# 3_baseband.net
KiCad netlist of a schematic drawn in Altium Designer
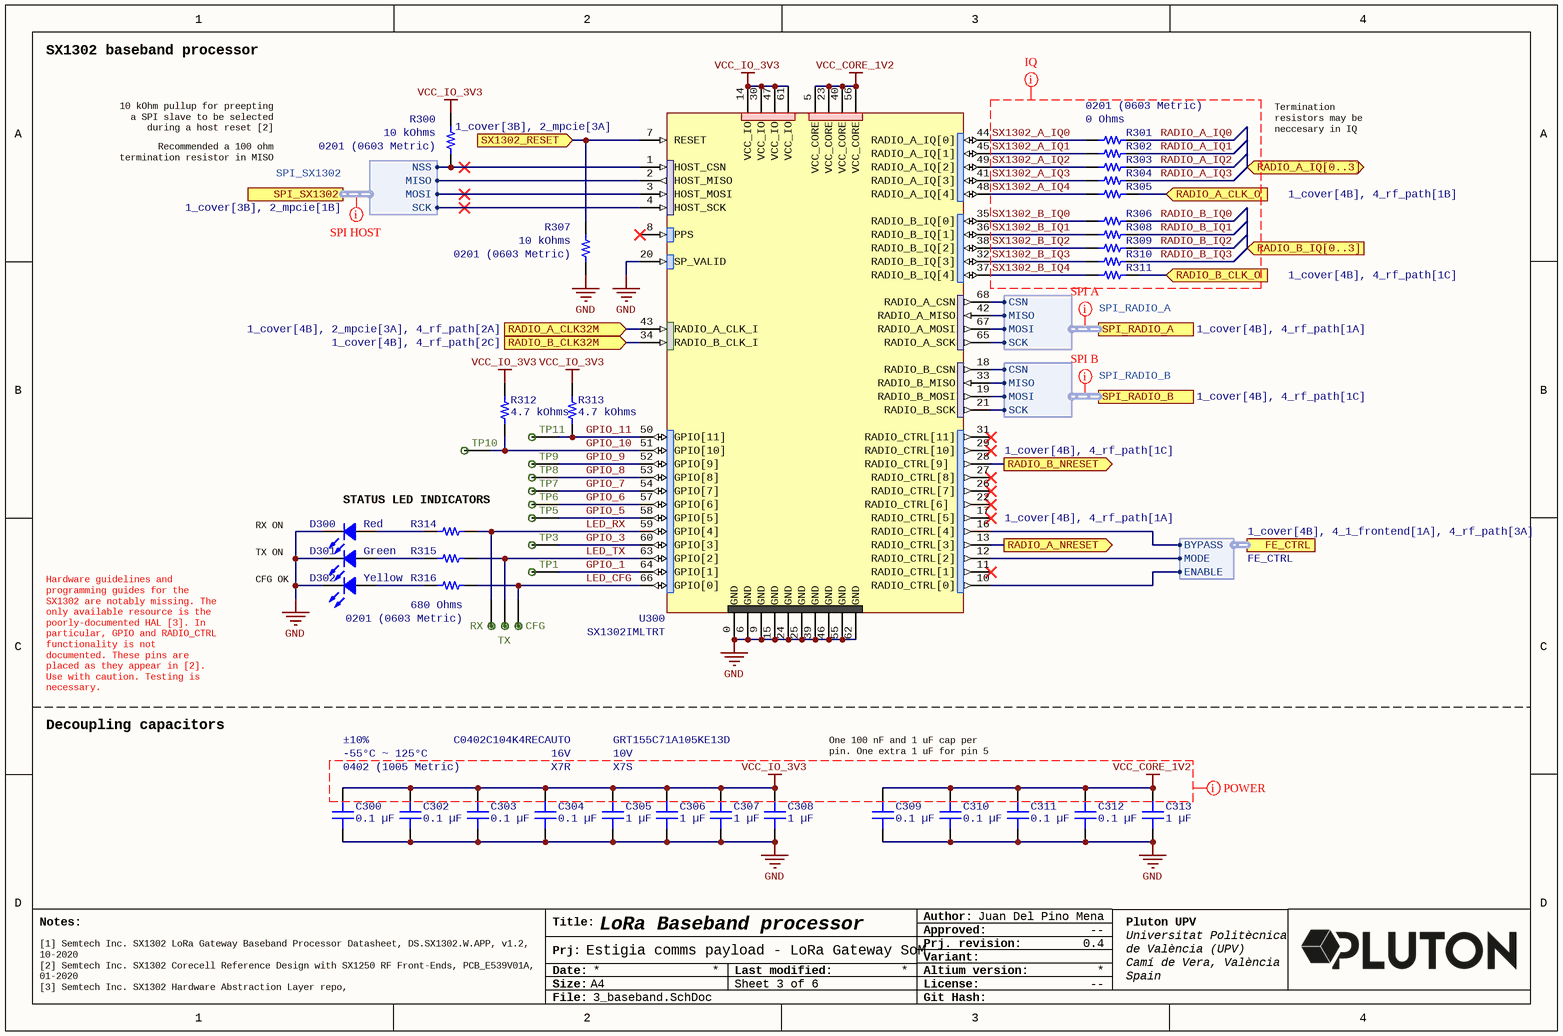
[diagram p0: 3_baseband.SchDoc]

(export (version "E")
  (design (tool "Eeschema 10.0.6"))
  (components
    (comp (ref "C300")
      (value "0.1 µF")
      (footprint "CAP 0402_1005")
      (description "CAP CER 0402 0.1UF 16V X7R 10%")
      (fields
        (field (name "PART NUMBER") "C0402C104K4RECAUTO")
        (field (name "MANUFACTURER") "KEMET")
        (field (name "OPERATING TEMPERATURE") "-55°C ~ 125°C")
        (field (name "PACKAGE / CASE") "0402 (1005 Metric)")
        (field (name "TEMPERATURE COEFFICIENT") "X7R")
        (field (name "TOLERANCE") "±10%")
        (field (name "VOLTAGE - RATED") "16V")
      )
      (libsource (lib "Celestial Altium Library - altium_library") (part "Capacitor"))
    )
    (comp (ref "C302")
      (value "0.1 µF")
      (footprint "CAP 0402_1005")
      (description "CAP CER 0402 0.1UF 16V X7R 10%")
      (fields (field (name "PART NUMBER") "C0402C104K4RECAUTO") (field (name "MANUFACTURER") "KEMET"))
      (libsource (lib "Celestial Altium Library - altium_library") (part "Capacitor"))
    )
    (comp (ref "C303")
      (value "0.1 µF")
      (footprint "CAP 0402_1005")
      (description "CAP CER 0402 0.1UF 16V X7R 10%")
      (fields (field (name "PART NUMBER") "C0402C104K4RECAUTO") (field (name "MANUFACTURER") "KEMET"))
      (libsource (lib "Celestial Altium Library - altium_library") (part "Capacitor"))
    )
    (comp (ref "C304")
      (value "0.1 µF")
      (footprint "CAP 0402_1005")
      (description "CAP CER 0402 0.1UF 16V X7R 10%")
      (fields (field (name "PART NUMBER") "C0402C104K4RECAUTO") (field (name "MANUFACTURER") "KEMET"))
      (libsource (lib "Celestial Altium Library - altium_library") (part "Capacitor"))
    )
    (comp (ref "C305")
      (value "1 µF")
      (footprint "CAP 0402_1005")
      (description "CAP CER 1UF 10V X7S 0402")
      (fields
        (field (name "PART NUMBER") "GRT155C71A105KE13D")
        (field (name "MANUFACTURER") "Murata Electronics")
        (field (name "TEMPERATURE COEFFICIENT") "X7S")
        (field (name "TOLERANCE") "±10%")
        (field (name "VOLTAGE - RATED") "10V")
      )
      (libsource (lib "Celestial Altium Library - altium_library") (part "Capacitor"))
    )
    (comp (ref "C306")
      (value "1 µF")
      (footprint "CAP 0402_1005")
      (description "CAP CER 1UF 10V X7S 0402")
      (fields
        (field (name "PART NUMBER") "GRT155C71A105KE13D")
        (field (name "MANUFACTURER") "Murata Electronics")
      )
      (libsource (lib "Celestial Altium Library - altium_library") (part "Capacitor"))
    )
    (comp (ref "C307")
      (value "1 µF")
      (footprint "CAP 0402_1005")
      (description "CAP CER 1UF 10V X7S 0402")
      (fields
        (field (name "PART NUMBER") "GRT155C71A105KE13D")
        (field (name "MANUFACTURER") "Murata Electronics")
      )
      (libsource (lib "Celestial Altium Library - altium_library") (part "Capacitor"))
    )
    (comp (ref "C308")
      (value "1 µF")
      (footprint "CAP 0402_1005")
      (description "CAP CER 1UF 10V X7S 0402")
      (fields
        (field (name "PART NUMBER") "GRT155C71A105KE13D")
        (field (name "MANUFACTURER") "Murata Electronics")
      )
      (libsource (lib "Celestial Altium Library - altium_library") (part "Capacitor"))
    )
    (comp (ref "C309")
      (value "0.1 µF")
      (footprint "CAP 0402_1005")
      (description "CAP CER 0402 0.1UF 16V X7R 10%")
      (fields (field (name "PART NUMBER") "C0402C104K4RECAUTO") (field (name "MANUFACTURER") "KEMET"))
      (libsource (lib "Celestial Altium Library - altium_library") (part "Capacitor"))
    )
    (comp (ref "C310")
      (value "0.1 µF")
      (footprint "CAP 0402_1005")
      (description "CAP CER 0402 0.1UF 16V X7R 10%")
      (fields (field (name "PART NUMBER") "C0402C104K4RECAUTO") (field (name "MANUFACTURER") "KEMET"))
      (libsource (lib "Celestial Altium Library - altium_library") (part "Capacitor"))
    )
    (comp (ref "C311")
      (value "0.1 µF")
      (footprint "CAP 0402_1005")
      (description "CAP CER 0402 0.1UF 16V X7R 10%")
      (fields (field (name "PART NUMBER") "C0402C104K4RECAUTO") (field (name "MANUFACTURER") "KEMET"))
      (libsource (lib "Celestial Altium Library - altium_library") (part "Capacitor"))
    )
    (comp (ref "C312")
      (value "0.1 µF")
      (footprint "CAP 0402_1005")
      (description "CAP CER 0402 0.1UF 16V X7R 10%")
      (fields (field (name "PART NUMBER") "C0402C104K4RECAUTO") (field (name "MANUFACTURER") "KEMET"))
      (libsource (lib "Celestial Altium Library - altium_library") (part "Capacitor"))
    )
    (comp (ref "C313")
      (value "1 µF")
      (footprint "CAP 0402_1005")
      (description "CAP CER 1UF 10V X7S 0402")
      (fields
        (field (name "PART NUMBER") "GRT155C71A105KE13D")
        (field (name "MANUFACTURER") "Murata Electronics")
      )
      (libsource (lib "Celestial Altium Library - altium_library") (part "Capacitor"))
    )
    (comp (ref "CFG")
      (value "~")
      (footprint "testpoints:testpoint_via")
      (description "Test point, thru-hole")
      (libsource (lib "testpoints") (part "TestPoint-VIA"))
    )
    (comp (ref "D300")
      (value "Red")
      (footprint "LED 0402_1005 RED")
      (description "LED RED CLEAR 2SMD")
      (fields
        (field (name "PART NUMBER") "EAST10053RA0")
        (field (name "COLOR") "Red")
        (field (name "MANUFACTURER") "Everlight Electronics Co Ltd")
      )
      (libsource (lib "Celestial Altium Library - altium_library") (part "LED"))
    )
    (comp (ref "D301")
      (value "Green")
      (footprint "LED 0402_1005 GREEN")
      (description "LED GREEN CLEAR 2SMD")
      (fields
        (field (name "PART NUMBER") "EAST10052GA0")
        (field (name "COLOR") "Green")
        (field (name "MANUFACTURER") "Everlight Electronics Co Ltd")
      )
      (libsource (lib "Celestial Altium Library - altium_library") (part "LED"))
    )
    (comp (ref "D302")
      (value "Yellow")
      (footprint "LED 0402_1005 YELLOW")
      (description "LED YELLOW CLEAR 1005 SMD")
      (fields
        (field (name "PART NUMBER") "FHY1105P-TR")
        (field (name "COLOR") "Yellow")
        (field (name "MANUFACTURER") "Stanley Electric Co")
      )
      (libsource (lib "Celestial Altium Library - altium_library") (part "LED"))
    )
    (comp (ref "R300")
      (value "10 kOhms")
      (footprint "RES 0201_0603")
      (description "RES SMD 10K OHM 1% 1/20W 0201")
      (fields
        (field (name "PART NUMBER") "AF0201FR-0710KL")
        (field (name "MANUFACTURER") "Yageo")
        (field (name "PACKAGE / CASE") "0201 (0603 Metric)")
      )
      (libsource (lib "Celestial Altium Library - altium_library") (part "Resistor"))
    )
    (comp (ref "R301")
      (value "0 Ohms")
      (footprint "RES 0201_0603")
      (description "RES SMD 0 OHM JUMPER 1/20W 0201")
      (fields
        (field (name "PART NUMBER") "AC0201JR-070RL")
        (field (name "DEVICE PACKAGE") "0201 (0603 Metric)")
        (field (name "MANUFACTURER") "Yageo")
      )
      (libsource (lib "Celestial Altium Library - altium_library") (part "Resistor"))
    )
    (comp (ref "R302")
      (value "0 Ohms")
      (footprint "RES 0201_0603")
      (description "RES SMD 0 OHM JUMPER 1/20W 0201")
      (fields (field (name "PART NUMBER") "AC0201JR-070RL") (field (name "MANUFACTURER") "Yageo"))
      (libsource (lib "Celestial Altium Library - altium_library") (part "Resistor"))
    )
    (comp (ref "R303")
      (value "0 Ohms")
      (footprint "RES 0201_0603")
      (description "RES SMD 0 OHM JUMPER 1/20W 0201")
      (fields (field (name "PART NUMBER") "AC0201JR-070RL") (field (name "MANUFACTURER") "Yageo"))
      (libsource (lib "Celestial Altium Library - altium_library") (part "Resistor"))
    )
    (comp (ref "R304")
      (value "0 Ohms")
      (footprint "RES 0201_0603")
      (description "RES SMD 0 OHM JUMPER 1/20W 0201")
      (fields (field (name "PART NUMBER") "AC0201JR-070RL") (field (name "MANUFACTURER") "Yageo"))
      (libsource (lib "Celestial Altium Library - altium_library") (part "Resistor"))
    )
    (comp (ref "R305")
      (value "0 Ohms")
      (footprint "RES 0201_0603")
      (description "RES SMD 0 OHM JUMPER 1/20W 0201")
      (fields (field (name "PART NUMBER") "AC0201JR-070RL") (field (name "MANUFACTURER") "Yageo"))
      (libsource (lib "Celestial Altium Library - altium_library") (part "Resistor"))
    )
    (comp (ref "R306")
      (value "0 Ohms")
      (footprint "RES 0201_0603")
      (description "RES SMD 0 OHM JUMPER 1/20W 0201")
      (fields (field (name "PART NUMBER") "AC0201JR-070RL") (field (name "MANUFACTURER") "Yageo"))
      (libsource (lib "Celestial Altium Library - altium_library") (part "Resistor"))
    )
    (comp (ref "R307")
      (value "10 kOhms")
      (footprint "RES 0201_0603")
      (description "RES SMD 10K OHM 1% 1/20W 0201")
      (fields
        (field (name "PART NUMBER") "AF0201FR-0710KL")
        (field (name "MANUFACTURER") "Yageo")
        (field (name "PACKAGE / CASE") "0201 (0603 Metric)")
      )
      (libsource (lib "Celestial Altium Library - altium_library") (part "Resistor"))
    )
    (comp (ref "R308")
      (value "0 Ohms")
      (footprint "RES 0201_0603")
      (description "RES SMD 0 OHM JUMPER 1/20W 0201")
      (fields (field (name "PART NUMBER") "AC0201JR-070RL") (field (name "MANUFACTURER") "Yageo"))
      (libsource (lib "Celestial Altium Library - altium_library") (part "Resistor"))
    )
    (comp (ref "R309")
      (value "0 Ohms")
      (footprint "RES 0201_0603")
      (description "RES SMD 0 OHM JUMPER 1/20W 0201")
      (fields (field (name "PART NUMBER") "AC0201JR-070RL") (field (name "MANUFACTURER") "Yageo"))
      (libsource (lib "Celestial Altium Library - altium_library") (part "Resistor"))
    )
    (comp (ref "R310")
      (value "0 Ohms")
      (footprint "RES 0201_0603")
      (description "RES SMD 0 OHM JUMPER 1/20W 0201")
      (fields (field (name "PART NUMBER") "AC0201JR-070RL") (field (name "MANUFACTURER") "Yageo"))
      (libsource (lib "Celestial Altium Library - altium_library") (part "Resistor"))
    )
    (comp (ref "R311")
      (value "0 Ohms")
      (footprint "RES 0201_0603")
      (description "RES SMD 0 OHM JUMPER 1/20W 0201")
      (fields (field (name "PART NUMBER") "AC0201JR-070RL") (field (name "MANUFACTURER") "Yageo"))
      (libsource (lib "Celestial Altium Library - altium_library") (part "Resistor"))
    )
    (comp (ref "R312")
      (value "4.7 kOhms")
      (footprint "RES 0201_0603")
      (description "RES SMD 4.7K OHM 1% 1/20W 0201")
      (fields (field (name "PART NUMBER") "AC0201FR-074K7L") (field (name "MANUFACTURER") "Yageo"))
      (libsource (lib "Celestial Altium Library - altium_library") (part "Resistor"))
    )
    (comp (ref "R313")
      (value "4.7 kOhms")
      (footprint "RES 0201_0603")
      (description "RES SMD 4.7K OHM 1% 1/20W 0201")
      (fields (field (name "PART NUMBER") "AC0201FR-074K7L") (field (name "MANUFACTURER") "Yageo"))
      (libsource (lib "Celestial Altium Library - altium_library") (part "Resistor"))
    )
    (comp (ref "R314")
      (value "680 Ohms")
      (footprint "RES 0201_0603")
      (description "RES 680 OHM 5% 1/20W 0201")
      (fields (field (name "PART NUMBER") "RC0201JR-07680RL") (field (name "MANUFACTURER") "Yageo"))
      (libsource (lib "Celestial Altium Library - altium_library") (part "Resistor"))
    )
    (comp (ref "R315")
      (value "680 Ohms")
      (footprint "RES 0201_0603")
      (description "RES 680 OHM 5% 1/20W 0201")
      (fields (field (name "PART NUMBER") "RC0201JR-07680RL") (field (name "MANUFACTURER") "Yageo"))
      (libsource (lib "Celestial Altium Library - altium_library") (part "Resistor"))
    )
    (comp (ref "R316")
      (value "680 Ohms")
      (footprint "RES 0201_0603")
      (description "RES 680 OHM 5% 1/20W 0201")
      (fields
        (field (name "PART NUMBER") "RC0201JR-07680RL")
        (field (name "DEVICE PACKAGE") "0201 (0603 Metric)")
        (field (name "MANUFACTURER") "Yageo")
      )
      (libsource (lib "Celestial Altium Library - altium_library") (part "Resistor"))
    )
    (comp (ref "RX")
      (value "~")
      (footprint "testpoints:testpoint_via")
      (description "Test point, thru-hole")
      (libsource (lib "testpoints") (part "TestPoint-VIA"))
    )
    (comp (ref "TP1")
      (value "~")
      (footprint "testpoints:testpoint_pad")
      (description "Test point, pad")
      (libsource (lib "testpoints") (part "TestPoint-PAD"))
    )
    (comp (ref "TP3")
      (value "~")
      (footprint "testpoints:testpoint_pad")
      (description "Test point, pad")
      (libsource (lib "testpoints") (part "TestPoint-PAD"))
    )
    (comp (ref "TP5")
      (value "~")
      (footprint "testpoints:testpoint_pad")
      (description "Test point, pad")
      (libsource (lib "testpoints") (part "TestPoint-PAD"))
    )
    (comp (ref "TP6")
      (value "~")
      (footprint "testpoints:testpoint_pad")
      (description "Test point, pad")
      (libsource (lib "testpoints") (part "TestPoint-PAD"))
    )
    (comp (ref "TP7")
      (value "~")
      (footprint "testpoints:testpoint_pad")
      (description "Test point, pad")
      (libsource (lib "testpoints") (part "TestPoint-PAD"))
    )
    (comp (ref "TP8")
      (value "~")
      (footprint "testpoints:testpoint_pad")
      (description "Test point, pad")
      (libsource (lib "testpoints") (part "TestPoint-PAD"))
    )
    (comp (ref "TP9")
      (value "~")
      (footprint "testpoints:testpoint_pad")
      (description "Test point, pad")
      (libsource (lib "testpoints") (part "TestPoint-PAD"))
    )
    (comp (ref "TP10")
      (value "~")
      (footprint "testpoints:testpoint_pad")
      (description "Test point, pad")
      (libsource (lib "testpoints") (part "TestPoint-PAD"))
    )
    (comp (ref "TP11")
      (value "~")
      (footprint "testpoints:testpoint_pad")
      (description "Test point, pad")
      (libsource (lib "testpoints") (part "TestPoint-PAD"))
    )
    (comp (ref "TX")
      (value "~")
      (footprint "testpoints:testpoint_via")
      (description "Test point, thru-hole")
      (libsource (lib "testpoints") (part "TestPoint-VIA"))
    )
    (comp (ref "U300")
      (value "SX1302IMLTRT")
      (footprint "ics:QFN-68")
      (description "Baseband LoRa chip for gateways")
      (libsource (lib "lora") (part "SX1302IMLTRT"))
    )
  )
  (nets
    (net (code "5") (name "/BYPASS") (class "Default")
      (node (ref "U300") (pin "16") (pinfunction "RADIO_CTRL[4]_16") (pintype "output"))
    )
    (net (code "6") (name "/ENABLE") (class "Default")
      (node (ref "U300") (pin "10") (pinfunction "RADIO_CTRL[0]_10") (pintype "output"))
    )
    (net (code "7") (name "/GPIO_1") (class "Default")
      (node (ref "TP1") (pin "0") (pinfunction "0_0") (pintype "passive"))
      (node (ref "U300") (pin "64") (pinfunction "GPIO[1]_64") (pintype "bidirectional"))
    )
    (net (code "8") (name "/GPIO_3") (class "Default")
      (node (ref "TP3") (pin "0") (pinfunction "0_0") (pintype "passive"))
      (node (ref "U300") (pin "60") (pinfunction "GPIO[3]_60") (pintype "bidirectional"))
    )
    (net (code "9") (name "/GPIO_5") (class "Default")
      (node (ref "TP5") (pin "0") (pinfunction "0_0") (pintype "passive"))
      (node (ref "U300") (pin "58") (pinfunction "GPIO[5]_58") (pintype "bidirectional"))
    )
    (net (code "10") (name "/GPIO_6") (class "Default")
      (node (ref "TP6") (pin "0") (pinfunction "0_0") (pintype "passive"))
      (node (ref "U300") (pin "57") (pinfunction "GPIO[6]_57") (pintype "bidirectional"))
    )
    (net (code "11") (name "/GPIO_7") (class "Default")
      (node (ref "TP7") (pin "0") (pinfunction "0_0") (pintype "passive"))
      (node (ref "U300") (pin "54") (pinfunction "GPIO[7]_54") (pintype "bidirectional"))
    )
    (net (code "12") (name "/GPIO_8") (class "Default")
      (node (ref "TP8") (pin "0") (pinfunction "0_0") (pintype "passive"))
      (node (ref "U300") (pin "53") (pinfunction "GPIO[8]_53") (pintype "bidirectional"))
    )
    (net (code "13") (name "/GPIO_9") (class "Default")
      (node (ref "TP9") (pin "0") (pinfunction "0_0") (pintype "passive"))
      (node (ref "U300") (pin "52") (pinfunction "GPIO[9]_52") (pintype "bidirectional"))
    )
    (net (code "14") (name "/GPIO_10") (class "Default")
      (node (ref "R312") (pin "1") (pinfunction "1_1") (pintype "passive"))
      (node (ref "TP10") (pin "0") (pinfunction "0_0") (pintype "passive"))
      (node (ref "U300") (pin "51") (pinfunction "GPIO[10]_51") (pintype "bidirectional"))
    )
    (net (code "15") (name "/GPIO_11") (class "Default")
      (node (ref "R313") (pin "1") (pinfunction "1_1") (pintype "passive"))
      (node (ref "TP11") (pin "0") (pinfunction "0_0") (pintype "passive"))
      (node (ref "U300") (pin "50") (pinfunction "GPIO[11]_50") (pintype "bidirectional"))
    )
    (net (code "16") (name "/LED_CFG") (class "Default")
      (node (ref "CFG") (pin "0") (pinfunction "0_0") (pintype "passive"))
      (node (ref "R316") (pin "2") (pinfunction "2_2") (pintype "passive"))
      (node (ref "U300") (pin "66") (pinfunction "GPIO[0]_66") (pintype "bidirectional"))
    )
    (net (code "17") (name "/LED_RX") (class "Default")
      (node (ref "R314") (pin "2") (pinfunction "2_2") (pintype "passive"))
      (node (ref "RX") (pin "0") (pinfunction "0_0") (pintype "passive"))
      (node (ref "U300") (pin "59") (pinfunction "GPIO[4]_59") (pintype "bidirectional"))
    )
    (net (code "18") (name "/LED_TX") (class "Default")
      (node (ref "R315") (pin "2") (pinfunction "2_2") (pintype "passive"))
      (node (ref "TX") (pin "0") (pinfunction "0_0") (pintype "passive"))
      (node (ref "U300") (pin "63") (pinfunction "GPIO[2]_63") (pintype "bidirectional"))
    )
    (net (code "19") (name "/MODE") (class "Default")
      (node (ref "U300") (pin "12") (pinfunction "RADIO_CTRL[2]_12") (pintype "output"))
    )
    (net (code "20") (name "/NSS") (class "Default")
      (node (ref "R300") (pin "2") (pinfunction "2_2") (pintype "passive"))
      (node (ref "U300") (pin "1") (pinfunction "HOST_CSN_1") (pintype "input"))
    )
    (net (code "21") (name "/RADIO_A_CLK32M") (class "Default")
      (node (ref "U300") (pin "43") (pinfunction "RADIO_A_CLK_I_43") (pintype "input"))
    )
    (net (code "22") (name "/RADIO_A_CLK_O") (class "Default")
      (node (ref "R305") (pin "2") (pinfunction "2_2") (pintype "passive"))
    )
    (net (code "23") (name "/RADIO_A_IQ0") (class "Default")
      (node (ref "R301") (pin "2") (pinfunction "2_2") (pintype "passive"))
    )
    (net (code "24") (name "/RADIO_A_IQ1") (class "Default")
      (node (ref "R302") (pin "2") (pinfunction "2_2") (pintype "passive"))
    )
    (net (code "25") (name "/RADIO_A_IQ2") (class "Default")
      (node (ref "R303") (pin "2") (pinfunction "2_2") (pintype "passive"))
    )
    (net (code "26") (name "/RADIO_A_IQ3") (class "Default")
      (node (ref "R304") (pin "2") (pinfunction "2_2") (pintype "passive"))
    )
    (net (code "28") (name "/RADIO_A_NRESET") (class "Default")
      (node (ref "U300") (pin "13") (pinfunction "RADIO_CTRL[3]_13") (pintype "output"))
    )
    (net (code "29") (name "/RADIO_B_CLK32M") (class "Default")
      (node (ref "U300") (pin "34") (pinfunction "RADIO_B_CLK_I_34") (pintype "input"))
    )
    (net (code "30") (name "/RADIO_B_CLK_O") (class "Default")
      (node (ref "R311") (pin "2") (pinfunction "2_2") (pintype "passive"))
    )
    (net (code "31") (name "/RADIO_B_IQ0") (class "Default")
      (node (ref "R306") (pin "2") (pinfunction "2_2") (pintype "passive"))
    )
    (net (code "32") (name "/RADIO_B_IQ1") (class "Default")
      (node (ref "R308") (pin "2") (pinfunction "2_2") (pintype "passive"))
    )
    (net (code "33") (name "/RADIO_B_IQ2") (class "Default")
      (node (ref "R309") (pin "2") (pinfunction "2_2") (pintype "passive"))
    )
    (net (code "34") (name "/RADIO_B_IQ3") (class "Default")
      (node (ref "R310") (pin "2") (pinfunction "2_2") (pintype "passive"))
    )
    (net (code "36") (name "/RADIO_B_NRESET") (class "Default")
      (node (ref "U300") (pin "28") (pinfunction "RADIO_CTRL[9]_28") (pintype "output"))
    )
    (net (code "37") (name "/SX1302_A_IQ0") (class "Default")
      (node (ref "R301") (pin "1") (pinfunction "1_1") (pintype "passive"))
      (node (ref "U300") (pin "44") (pinfunction "RADIO_A_IQ[0]_44") (pintype "bidirectional"))
    )
    (net (code "38") (name "/SX1302_A_IQ1") (class "Default")
      (node (ref "R302") (pin "1") (pinfunction "1_1") (pintype "passive"))
      (node (ref "U300") (pin "45") (pinfunction "RADIO_A_IQ[1]_45") (pintype "bidirectional"))
    )
    (net (code "39") (name "/SX1302_A_IQ2") (class "Default")
      (node (ref "R303") (pin "1") (pinfunction "1_1") (pintype "passive"))
      (node (ref "U300") (pin "49") (pinfunction "RADIO_A_IQ[2]_49") (pintype "bidirectional"))
    )
    (net (code "40") (name "/SX1302_A_IQ3") (class "Default")
      (node (ref "R304") (pin "1") (pinfunction "1_1") (pintype "passive"))
      (node (ref "U300") (pin "41") (pinfunction "RADIO_A_IQ[3]_41") (pintype "bidirectional"))
    )
    (net (code "41") (name "/SX1302_A_IQ4") (class "Default")
      (node (ref "R305") (pin "1") (pinfunction "1_1") (pintype "passive"))
      (node (ref "U300") (pin "48") (pinfunction "RADIO_A_IQ[4]_48") (pintype "bidirectional"))
    )
    (net (code "42") (name "/SX1302_B_IQ0") (class "Default")
      (node (ref "R306") (pin "1") (pinfunction "1_1") (pintype "passive"))
      (node (ref "U300") (pin "35") (pinfunction "RADIO_B_IQ[0]_35") (pintype "bidirectional"))
    )
    (net (code "43") (name "/SX1302_B_IQ1") (class "Default")
      (node (ref "R308") (pin "1") (pinfunction "1_1") (pintype "passive"))
      (node (ref "U300") (pin "36") (pinfunction "RADIO_B_IQ[1]_36") (pintype "bidirectional"))
    )
    (net (code "44") (name "/SX1302_B_IQ2") (class "Default")
      (node (ref "R309") (pin "1") (pinfunction "1_1") (pintype "passive"))
      (node (ref "U300") (pin "38") (pinfunction "RADIO_B_IQ[2]_38") (pintype "bidirectional"))
    )
    (net (code "45") (name "/SX1302_B_IQ3") (class "Default")
      (node (ref "R310") (pin "1") (pinfunction "1_1") (pintype "passive"))
      (node (ref "U300") (pin "32") (pinfunction "RADIO_B_IQ[3]_32") (pintype "bidirectional"))
    )
    (net (code "46") (name "/SX1302_B_IQ4") (class "Default")
      (node (ref "R311") (pin "1") (pinfunction "1_1") (pintype "passive"))
      (node (ref "U300") (pin "37") (pinfunction "RADIO_B_IQ[4]_37") (pintype "bidirectional"))
    )
    (net (code "47") (name "/SX1302_RESET") (class "Default")
      (node (ref "R307") (pin "1") (pinfunction "1_1") (pintype "passive"))
      (node (ref "U300") (pin "7") (pinfunction "RESET_7") (pintype "input"))
    )
    (net (code "52") (name "GND") (class "Default")
      (node (ref "C300") (pin "1") (pinfunction "1_1") (pintype "passive"))
      (node (ref "C302") (pin "1") (pinfunction "1_1") (pintype "passive"))
      (node (ref "C303") (pin "1") (pinfunction "1_1") (pintype "passive"))
      (node (ref "C304") (pin "1") (pinfunction "1_1") (pintype "passive"))
      (node (ref "C305") (pin "1") (pinfunction "1_1") (pintype "passive"))
      (node (ref "C306") (pin "1") (pinfunction "1_1") (pintype "passive"))
      (node (ref "C307") (pin "1") (pinfunction "1_1") (pintype "passive"))
      (node (ref "C308") (pin "1") (pinfunction "1_1") (pintype "passive"))
      (node (ref "C309") (pin "1") (pinfunction "1_1") (pintype "passive"))
      (node (ref "C310") (pin "1") (pinfunction "1_1") (pintype "passive"))
      (node (ref "C311") (pin "1") (pinfunction "1_1") (pintype "passive"))
      (node (ref "C312") (pin "1") (pinfunction "1_1") (pintype "passive"))
      (node (ref "C313") (pin "1") (pinfunction "1_1") (pintype "passive"))
      (node (ref "D300") (pin "2") (pinfunction "2_2") (pintype "passive"))
      (node (ref "D301") (pin "2") (pinfunction "2_2") (pintype "passive"))
      (node (ref "D302") (pin "2") (pinfunction "2_2") (pintype "passive"))
      (node (ref "R307") (pin "2") (pinfunction "2_2") (pintype "passive"))
      (node (ref "U300") (pin "0") (pinfunction "GND_0") (pintype "power_in"))
      (node (ref "U300") (pin "15") (pinfunction "GND_15") (pintype "power_in"))
      (node (ref "U300") (pin "20") (pinfunction "SP_VALID_20") (pintype "input"))
      (node (ref "U300") (pin "24") (pinfunction "GND_24") (pintype "power_in"))
      (node (ref "U300") (pin "25") (pinfunction "GND_25") (pintype "power_in"))
      (node (ref "U300") (pin "39") (pinfunction "GND_39") (pintype "power_in"))
      (node (ref "U300") (pin "46") (pinfunction "GND_46") (pintype "power_in"))
      (node (ref "U300") (pin "55") (pinfunction "GND_55") (pintype "power_in"))
      (node (ref "U300") (pin "6") (pinfunction "GND_6") (pintype "power_in"))
      (node (ref "U300") (pin "62") (pinfunction "GND_62") (pintype "power_in"))
      (node (ref "U300") (pin "9") (pinfunction "GND_9") (pintype "power_in"))
    )
    (net (code "53") (name "Net-(D300-Pad1)") (class "Default")
      (node (ref "D300") (pin "1") (pinfunction "1_1") (pintype "passive"))
      (node (ref "R314") (pin "1") (pinfunction "1_1") (pintype "passive"))
    )
    (net (code "54") (name "Net-(D301-Pad1)") (class "Default")
      (node (ref "D301") (pin "1") (pinfunction "1_1") (pintype "passive"))
      (node (ref "R315") (pin "1") (pinfunction "1_1") (pintype "passive"))
    )
    (net (code "55") (name "Net-(D302-Pad1)") (class "Default")
      (node (ref "D302") (pin "1") (pinfunction "1_1") (pintype "passive"))
      (node (ref "R316") (pin "1") (pinfunction "1_1") (pintype "passive"))
    )
    (net (code "56") (name "VCC_CORE_1V2") (class "Default")
      (node (ref "C309") (pin "2") (pinfunction "2_2") (pintype "passive"))
      (node (ref "C310") (pin "2") (pinfunction "2_2") (pintype "passive"))
      (node (ref "C311") (pin "2") (pinfunction "2_2") (pintype "passive"))
      (node (ref "C312") (pin "2") (pinfunction "2_2") (pintype "passive"))
      (node (ref "C313") (pin "2") (pinfunction "2_2") (pintype "passive"))
      (node (ref "U300") (pin "23") (pinfunction "VCC_CORE_23") (pintype "power_in"))
      (node (ref "U300") (pin "40") (pinfunction "VCC_CORE_40") (pintype "power_in"))
      (node (ref "U300") (pin "5") (pinfunction "VCC_CORE_5") (pintype "power_in"))
      (node (ref "U300") (pin "56") (pinfunction "VCC_CORE_56") (pintype "power_in"))
    )
    (net (code "57") (name "VCC_IO_3V3") (class "Default")
      (node (ref "C300") (pin "2") (pinfunction "2_2") (pintype "passive"))
      (node (ref "C302") (pin "2") (pinfunction "2_2") (pintype "passive"))
      (node (ref "C303") (pin "2") (pinfunction "2_2") (pintype "passive"))
      (node (ref "C304") (pin "2") (pinfunction "2_2") (pintype "passive"))
      (node (ref "C305") (pin "2") (pinfunction "2_2") (pintype "passive"))
      (node (ref "C306") (pin "2") (pinfunction "2_2") (pintype "passive"))
      (node (ref "C307") (pin "2") (pinfunction "2_2") (pintype "passive"))
      (node (ref "C308") (pin "2") (pinfunction "2_2") (pintype "passive"))
      (node (ref "R300") (pin "1") (pinfunction "1_1") (pintype "passive"))
      (node (ref "R312") (pin "2") (pinfunction "2_2") (pintype "passive"))
      (node (ref "R313") (pin "2") (pinfunction "2_2") (pintype "passive"))
      (node (ref "U300") (pin "14") (pinfunction "VCC_IO_14") (pintype "power_in"))
      (node (ref "U300") (pin "30") (pinfunction "VCC_IO_30") (pintype "power_in"))
      (node (ref "U300") (pin "47") (pinfunction "VCC_IO_47") (pintype "power_in"))
      (node (ref "U300") (pin "61") (pinfunction "VCC_IO_61") (pintype "power_in"))
    )
    (net (code "58") (name "unconnected-(U300-HOST_MISO-Pad2)") (class "Default")
      (node (ref "U300") (pin "2") (pinfunction "HOST_MISO_2") (pintype "output"))
    )
    (net (code "59") (name "unconnected-(U300-HOST_MOSI-Pad3)") (class "Default")
      (node (ref "U300") (pin "3") (pinfunction "HOST_MOSI_3") (pintype "input"))
    )
    (net (code "60") (name "unconnected-(U300-HOST_SCK-Pad4)") (class "Default")
      (node (ref "U300") (pin "4") (pinfunction "HOST_SCK_4") (pintype "input"))
    )
    (net (code "61") (name "unconnected-(U300-PPS-Pad8)") (class "Default")
      (node (ref "U300") (pin "8") (pinfunction "PPS_8") (pintype "input+no_connect"))
    )
    (net (code "62") (name "unconnected-(U300-RADIO_A_CSN-Pad68)") (class "Default")
      (node (ref "U300") (pin "68") (pinfunction "RADIO_A_CSN_68") (pintype "output"))
    )
    (net (code "63") (name "unconnected-(U300-RADIO_A_MISO-Pad42)") (class "Default")
      (node (ref "U300") (pin "42") (pinfunction "RADIO_A_MISO_42") (pintype "input"))
    )
    (net (code "64") (name "unconnected-(U300-RADIO_A_MOSI-Pad67)") (class "Default")
      (node (ref "U300") (pin "67") (pinfunction "RADIO_A_MOSI_67") (pintype "output"))
    )
    (net (code "65") (name "unconnected-(U300-RADIO_A_SCK-Pad65)") (class "Default")
      (node (ref "U300") (pin "65") (pinfunction "RADIO_A_SCK_65") (pintype "output"))
    )
    (net (code "66") (name "unconnected-(U300-RADIO_B_CSN-Pad18)") (class "Default")
      (node (ref "U300") (pin "18") (pinfunction "RADIO_B_CSN_18") (pintype "output"))
    )
    (net (code "67") (name "unconnected-(U300-RADIO_B_MISO-Pad33)") (class "Default")
      (node (ref "U300") (pin "33") (pinfunction "RADIO_B_MISO_33") (pintype "input"))
    )
    (net (code "68") (name "unconnected-(U300-RADIO_B_MOSI-Pad19)") (class "Default")
      (node (ref "U300") (pin "19") (pinfunction "RADIO_B_MOSI_19") (pintype "output"))
    )
    (net (code "69") (name "unconnected-(U300-RADIO_B_SCK-Pad21)") (class "Default")
      (node (ref "U300") (pin "21") (pinfunction "RADIO_B_SCK_21") (pintype "output"))
    )
    (net (code "70") (name "unconnected-(U300-RADIO_CTRL[1]-Pad11)") (class "Default")
      (node (ref "U300") (pin "11") (pinfunction "RADIO_CTRL[1]_11") (pintype "output+no_connect"))
    )
    (net (code "71") (name "unconnected-(U300-RADIO_CTRL[5]-Pad17)") (class "Default")
      (node (ref "U300") (pin "17") (pinfunction "RADIO_CTRL[5]_17") (pintype "output+no_connect"))
    )
    (net (code "72") (name "unconnected-(U300-RADIO_CTRL[6]-Pad22)") (class "Default")
      (node (ref "U300") (pin "22") (pinfunction "RADIO_CTRL[6]_22") (pintype "output+no_connect"))
    )
    (net (code "73") (name "unconnected-(U300-RADIO_CTRL[7]-Pad26)") (class "Default")
      (node (ref "U300") (pin "26") (pinfunction "RADIO_CTRL[7]_26") (pintype "output+no_connect"))
    )
    (net (code "74") (name "unconnected-(U300-RADIO_CTRL[8]-Pad27)") (class "Default")
      (node (ref "U300") (pin "27") (pinfunction "RADIO_CTRL[8]_27") (pintype "output+no_connect"))
    )
    (net (code "75") (name "unconnected-(U300-RADIO_CTRL[10]-Pad29)") (class "Default")
      (node (ref "U300") (pin "29") (pinfunction "RADIO_CTRL[10]_29") (pintype "output+no_connect"))
    )
    (net (code "76") (name "unconnected-(U300-RADIO_CTRL[11]-Pad31)") (class "Default")
      (node (ref "U300") (pin "31") (pinfunction "RADIO_CTRL[11]_31") (pintype "output+no_connect"))
    )
  )
)
